# Simulador_Sensor_Hall.net
KiCad netlist of a schematic drawn in EAGLE
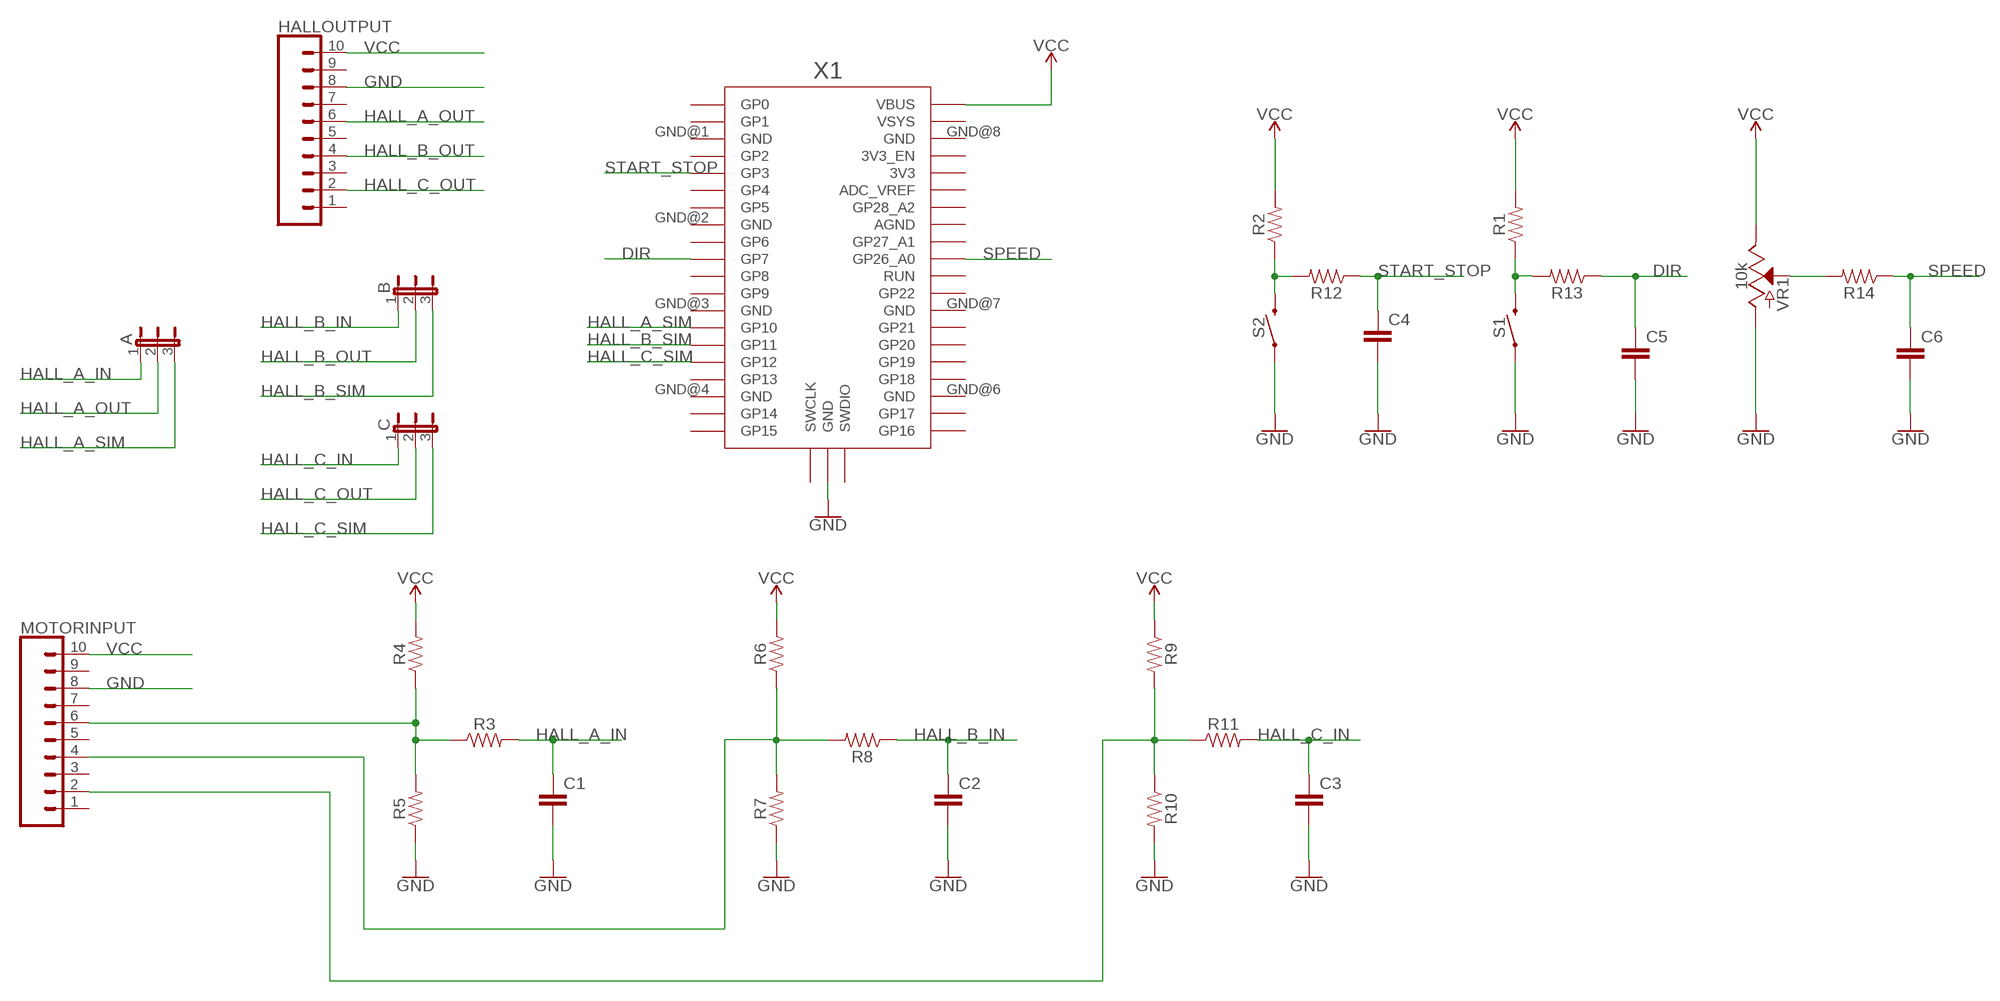
[diagram p0: schematic, sheet 1]

(export (version "E")
  (design (tool "Eeschema 10.0.6"))
  (components
    (comp (ref "A")
      (value "JP2E")
      (footprint "eagle-import:JP2")
      (libsource (lib "eagle-import") (part "JP2E"))
    )
    (comp (ref "B")
      (value "JP2E")
      (footprint "eagle-import:JP2")
      (libsource (lib "eagle-import") (part "JP2E"))
    )
    (comp (ref "C")
      (value "JP2E")
      (footprint "eagle-import:JP2")
      (libsource (lib "eagle-import") (part "JP2E"))
    )
    (comp (ref "C1")
      (value "C-EUC0805K")
      (footprint "eagle-import:C0805K")
      (libsource (lib "eagle-import") (part "C-EUC0805K"))
    )
    (comp (ref "C2")
      (value "C-EUC0805K")
      (footprint "eagle-import:C0805K")
      (libsource (lib "eagle-import") (part "C-EUC0805K"))
    )
    (comp (ref "C3")
      (value "C-EUC0805K")
      (footprint "eagle-import:C0805K")
      (libsource (lib "eagle-import") (part "C-EUC0805K"))
    )
    (comp (ref "C4")
      (value "C-EUC0805K")
      (footprint "eagle-import:C0805K")
      (libsource (lib "eagle-import") (part "C-EUC0805K"))
    )
    (comp (ref "C5")
      (value "C-EUC0805K")
      (footprint "eagle-import:C0805K")
      (libsource (lib "eagle-import") (part "C-EUC0805K"))
    )
    (comp (ref "C6")
      (value "C-EUC0805K")
      (footprint "eagle-import:C0805K")
      (libsource (lib "eagle-import") (part "C-EUC0805K"))
    )
    (comp (ref "HALLOUTPUT")
      (value "CONN_10\"")
      (footprint "eagle-import:1X10")
      (libsource (lib "eagle-import") (part "CONN_10{dblquote}"))
    )
    (comp (ref "MOTORINPUT")
      (value "CONN_10\"")
      (footprint "eagle-import:1X10")
      (libsource (lib "eagle-import") (part "CONN_10{dblquote}"))
    )
    (comp (ref "R1")
      (value "RESISTOR0805")
      (footprint "eagle-import:0805")
      (libsource (lib "eagle-import") (part "RESISTOR0805"))
    )
    (comp (ref "R2")
      (value "RESISTOR0805")
      (footprint "eagle-import:0805")
      (libsource (lib "eagle-import") (part "RESISTOR0805"))
    )
    (comp (ref "R3")
      (value "RESISTOR0805")
      (footprint "eagle-import:0805")
      (libsource (lib "eagle-import") (part "RESISTOR0805"))
    )
    (comp (ref "R4")
      (value "RESISTOR0805")
      (footprint "eagle-import:0805")
      (libsource (lib "eagle-import") (part "RESISTOR0805"))
    )
    (comp (ref "R5")
      (value "RESISTOR0805")
      (footprint "eagle-import:0805")
      (libsource (lib "eagle-import") (part "RESISTOR0805"))
    )
    (comp (ref "R6")
      (value "RESISTOR0805")
      (footprint "eagle-import:0805")
      (libsource (lib "eagle-import") (part "RESISTOR0805"))
    )
    (comp (ref "R7")
      (value "RESISTOR0805")
      (footprint "eagle-import:0805")
      (libsource (lib "eagle-import") (part "RESISTOR0805"))
    )
    (comp (ref "R8")
      (value "RESISTOR0805")
      (footprint "eagle-import:0805")
      (libsource (lib "eagle-import") (part "RESISTOR0805"))
    )
    (comp (ref "R9")
      (value "RESISTOR0805")
      (footprint "eagle-import:0805")
      (libsource (lib "eagle-import") (part "RESISTOR0805"))
    )
    (comp (ref "R10")
      (value "RESISTOR0805")
      (footprint "eagle-import:0805")
      (libsource (lib "eagle-import") (part "RESISTOR0805"))
    )
    (comp (ref "R11")
      (value "RESISTOR0805")
      (footprint "eagle-import:0805")
      (libsource (lib "eagle-import") (part "RESISTOR0805"))
    )
    (comp (ref "R12")
      (value "RESISTOR0805")
      (footprint "eagle-import:0805")
      (libsource (lib "eagle-import") (part "RESISTOR0805"))
    )
    (comp (ref "R13")
      (value "RESISTOR0805")
      (footprint "eagle-import:0805")
      (libsource (lib "eagle-import") (part "RESISTOR0805"))
    )
    (comp (ref "R14")
      (value "RESISTOR0805")
      (footprint "eagle-import:0805")
      (libsource (lib "eagle-import") (part "RESISTOR0805"))
    )
    (comp (ref "S1")
      (value "MOMENTARY-SWITCH-SPST-SMD-6.2MM-TALL")
      (footprint "eagle-import:TACTILE_SWITCH_SMD_6.2MM_TALL")
      (libsource (lib "eagle-import") (part "MOMENTARY-SWITCH-SPST-SMD-6.2MM-TALL"))
    )
    (comp (ref "S2")
      (value "MOMENTARY-SWITCH-SPST-SMD-6.2MM-TALL")
      (footprint "eagle-import:TACTILE_SWITCH_SMD_6.2MM_TALL")
      (libsource (lib "eagle-import") (part "MOMENTARY-SWITCH-SPST-SMD-6.2MM-TALL"))
    )
    (comp (ref "VR1")
      (value "10k")
      (footprint "eagle-import:POT-PTH-ALPS")
      (libsource (lib "eagle-import") (part "POTENTIOMETER-PTH-9MM-1/20W-20%"))
    )
    (comp (ref "X1")
      (value "RPI_PICO_IG-TH")
      (footprint "eagle-import:RPI_PICO_TH")
      (libsource (lib "eagle-import") (part "RPI_PICO_IG-TH"))
    )
  )
  (nets
    (net (code "1") (name "/DIR") (class "Default")
      (node (ref "C5") (pin "1") (pinfunction "1_1") (pintype "passive"))
      (node (ref "R13") (pin "1") (pinfunction "1_1") (pintype "passive"))
      (node (ref "X1") (pin "GP7") (pinfunction "GP7_GP7") (pintype "bidirectional"))
    )
    (net (code "2") (name "/HALL_A_IN") (class "Default")
      (node (ref "A") (pin "1") (pinfunction "1_1") (pintype "passive"))
      (node (ref "C1") (pin "1") (pinfunction "1_1") (pintype "passive"))
      (node (ref "R3") (pin "2") (pinfunction "2_2") (pintype "passive"))
    )
    (net (code "3") (name "/HALL_A_OUT") (class "Default")
      (node (ref "A") (pin "2") (pinfunction "2_2") (pintype "passive"))
      (node (ref "HALLOUTPUT") (pin "6") (pinfunction "6_6") (pintype "passive"))
    )
    (net (code "4") (name "/HALL_A_SIM") (class "Default")
      (node (ref "A") (pin "3") (pinfunction "3_3") (pintype "passive"))
      (node (ref "X1") (pin "GP10") (pinfunction "GP10_GP10") (pintype "bidirectional"))
    )
    (net (code "5") (name "/HALL_B_IN") (class "Default")
      (node (ref "B") (pin "1") (pinfunction "1_1") (pintype "passive"))
      (node (ref "C2") (pin "1") (pinfunction "1_1") (pintype "passive"))
      (node (ref "R8") (pin "1") (pinfunction "1_1") (pintype "passive"))
    )
    (net (code "6") (name "/HALL_B_OUT") (class "Default")
      (node (ref "B") (pin "2") (pinfunction "2_2") (pintype "passive"))
      (node (ref "HALLOUTPUT") (pin "4") (pinfunction "4_4") (pintype "passive"))
    )
    (net (code "7") (name "/HALL_B_SIM") (class "Default")
      (node (ref "B") (pin "3") (pinfunction "3_3") (pintype "passive"))
      (node (ref "X1") (pin "GP11") (pinfunction "GP11_GP11") (pintype "bidirectional"))
    )
    (net (code "8") (name "/HALL_C_IN") (class "Default")
      (node (ref "C") (pin "1") (pinfunction "1_1") (pintype "passive"))
      (node (ref "C3") (pin "1") (pinfunction "1_1") (pintype "passive"))
      (node (ref "R11") (pin "2") (pinfunction "2_2") (pintype "passive"))
    )
    (net (code "9") (name "/HALL_C_OUT") (class "Default")
      (node (ref "C") (pin "2") (pinfunction "2_2") (pintype "passive"))
      (node (ref "HALLOUTPUT") (pin "2") (pinfunction "2_2") (pintype "passive"))
    )
    (net (code "10") (name "/HALL_C_SIM") (class "Default")
      (node (ref "C") (pin "3") (pinfunction "3_3") (pintype "passive"))
      (node (ref "X1") (pin "GP12") (pinfunction "GP12_GP12") (pintype "bidirectional"))
    )
    (net (code "11") (name "/SPEED") (class "Default")
      (node (ref "C6") (pin "1") (pinfunction "1_1") (pintype "passive"))
      (node (ref "R14") (pin "1") (pinfunction "1_1") (pintype "passive"))
      (node (ref "X1") (pin "GP26_A0") (pinfunction "GP26_A0_GP26_A0") (pintype "bidirectional"))
    )
    (net (code "12") (name "/START_STOP") (class "Default")
      (node (ref "C4") (pin "1") (pinfunction "1_1") (pintype "passive"))
      (node (ref "R12") (pin "1") (pinfunction "1_1") (pintype "passive"))
      (node (ref "X1") (pin "GP3") (pinfunction "GP3_GP3") (pintype "bidirectional"))
    )
    (net (code "13") (name "GND") (class "Default")
      (node (ref "C1") (pin "2") (pinfunction "2_2") (pintype "passive"))
      (node (ref "C2") (pin "2") (pinfunction "2_2") (pintype "passive"))
      (node (ref "C3") (pin "2") (pinfunction "2_2") (pintype "passive"))
      (node (ref "C4") (pin "2") (pinfunction "2_2") (pintype "passive"))
      (node (ref "C5") (pin "2") (pinfunction "2_2") (pintype "passive"))
      (node (ref "C6") (pin "2") (pinfunction "2_2") (pintype "passive"))
      (node (ref "HALLOUTPUT") (pin "8") (pinfunction "8_8") (pintype "passive"))
      (node (ref "MOTORINPUT") (pin "8") (pinfunction "8_8") (pintype "passive"))
      (node (ref "R10") (pin "2") (pinfunction "2_2") (pintype "passive"))
      (node (ref "R5") (pin "1") (pinfunction "1_1") (pintype "passive"))
      (node (ref "R7") (pin "1") (pinfunction "1_1") (pintype "passive"))
      (node (ref "S1") (pin "A2") (pinfunction "1_A2") (pintype "passive"))
      (node (ref "S2") (pin "A2") (pinfunction "1_A2") (pintype "passive"))
      (node (ref "VR1") (pin "P$3") (pinfunction "A_P$3") (pintype "passive"))
      (node (ref "X1") (pin "GND@5") (pinfunction "GND_GND@5") (pintype "bidirectional"))
    )
    (net (code "14") (name "Net-(MOTORINPUT-Pad2)") (class "Default")
      (node (ref "MOTORINPUT") (pin "2") (pinfunction "2_2") (pintype "passive"))
      (node (ref "R10") (pin "1") (pinfunction "1_1") (pintype "passive"))
      (node (ref "R11") (pin "1") (pinfunction "1_1") (pintype "passive"))
      (node (ref "R9") (pin "2") (pinfunction "2_2") (pintype "passive"))
    )
    (net (code "15") (name "Net-(MOTORINPUT-Pad4)") (class "Default")
      (node (ref "MOTORINPUT") (pin "4") (pinfunction "4_4") (pintype "passive"))
      (node (ref "R6") (pin "1") (pinfunction "1_1") (pintype "passive"))
      (node (ref "R7") (pin "2") (pinfunction "2_2") (pintype "passive"))
      (node (ref "R8") (pin "2") (pinfunction "2_2") (pintype "passive"))
    )
    (net (code "16") (name "Net-(MOTORINPUT-Pad6)") (class "Default")
      (node (ref "MOTORINPUT") (pin "6") (pinfunction "6_6") (pintype "passive"))
      (node (ref "R3") (pin "1") (pinfunction "1_1") (pintype "passive"))
      (node (ref "R4") (pin "1") (pinfunction "1_1") (pintype "passive"))
      (node (ref "R5") (pin "2") (pinfunction "2_2") (pintype "passive"))
    )
    (net (code "17") (name "Net-(S1-2)") (class "Default")
      (node (ref "R1") (pin "1") (pinfunction "1_1") (pintype "passive"))
      (node (ref "R13") (pin "2") (pinfunction "2_2") (pintype "passive"))
      (node (ref "S1") (pin "B2") (pinfunction "2_B2") (pintype "passive"))
    )
    (net (code "18") (name "Net-(S2-2)") (class "Default")
      (node (ref "R12") (pin "2") (pinfunction "2_2") (pintype "passive"))
      (node (ref "R2") (pin "1") (pinfunction "1_1") (pintype "passive"))
      (node (ref "S2") (pin "B2") (pinfunction "2_B2") (pintype "passive"))
    )
    (net (code "19") (name "Net-(VR1-S)") (class "Default")
      (node (ref "R14") (pin "2") (pinfunction "2_2") (pintype "passive"))
      (node (ref "VR1") (pin "P$2") (pinfunction "S_P$2") (pintype "passive"))
    )
    (net (code "20") (name "VCC") (class "Default")
      (node (ref "HALLOUTPUT") (pin "10") (pinfunction "10_10") (pintype "passive"))
      (node (ref "MOTORINPUT") (pin "10") (pinfunction "10_10") (pintype "passive"))
      (node (ref "R1") (pin "2") (pinfunction "2_2") (pintype "passive"))
      (node (ref "R2") (pin "2") (pinfunction "2_2") (pintype "passive"))
      (node (ref "R4") (pin "2") (pinfunction "2_2") (pintype "passive"))
      (node (ref "R6") (pin "2") (pinfunction "2_2") (pintype "passive"))
      (node (ref "R9") (pin "1") (pinfunction "1_1") (pintype "passive"))
      (node (ref "VR1") (pin "P$1") (pinfunction "E_P$1") (pintype "passive"))
      (node (ref "X1") (pin "VBUS") (pinfunction "VBUS_VBUS") (pintype "bidirectional"))
    )
    (net (code "21") (name "unconnected-(HALLOUTPUT-Pad1)") (class "Default")
      (node (ref "HALLOUTPUT") (pin "1") (pinfunction "1_1") (pintype "passive"))
    )
    (net (code "22") (name "unconnected-(HALLOUTPUT-Pad3)") (class "Default")
      (node (ref "HALLOUTPUT") (pin "3") (pinfunction "3_3") (pintype "passive"))
    )
    (net (code "23") (name "unconnected-(HALLOUTPUT-Pad5)") (class "Default")
      (node (ref "HALLOUTPUT") (pin "5") (pinfunction "5_5") (pintype "passive"))
    )
    (net (code "24") (name "unconnected-(HALLOUTPUT-Pad7)") (class "Default")
      (node (ref "HALLOUTPUT") (pin "7") (pinfunction "7_7") (pintype "passive"))
    )
    (net (code "25") (name "unconnected-(HALLOUTPUT-Pad9)") (class "Default")
      (node (ref "HALLOUTPUT") (pin "9") (pinfunction "9_9") (pintype "passive"))
    )
    (net (code "26") (name "unconnected-(MOTORINPUT-Pad1)") (class "Default")
      (node (ref "MOTORINPUT") (pin "1") (pinfunction "1_1") (pintype "passive"))
    )
    (net (code "27") (name "unconnected-(MOTORINPUT-Pad3)") (class "Default")
      (node (ref "MOTORINPUT") (pin "3") (pinfunction "3_3") (pintype "passive"))
    )
    (net (code "28") (name "unconnected-(MOTORINPUT-Pad5)") (class "Default")
      (node (ref "MOTORINPUT") (pin "5") (pinfunction "5_5") (pintype "passive"))
    )
    (net (code "29") (name "unconnected-(MOTORINPUT-Pad7)") (class "Default")
      (node (ref "MOTORINPUT") (pin "7") (pinfunction "7_7") (pintype "passive"))
    )
    (net (code "30") (name "unconnected-(MOTORINPUT-Pad9)") (class "Default")
      (node (ref "MOTORINPUT") (pin "9") (pinfunction "9_9") (pintype "passive"))
    )
    (net (code "31") (name "unconnected-(X1-GND-PadGND@1)") (class "Default")
      (node (ref "X1") (pin "GND@1") (pinfunction "GND_GND@1") (pintype "bidirectional"))
    )
    (net (code "32") (name "unconnected-(X1-GND-PadGND@2)") (class "Default")
      (node (ref "X1") (pin "GND@2") (pinfunction "GND_GND@2") (pintype "bidirectional"))
    )
    (net (code "33") (name "unconnected-(X1-GND-PadGND@3)") (class "Default")
      (node (ref "X1") (pin "GND@3") (pinfunction "GND_GND@3") (pintype "bidirectional"))
    )
    (net (code "34") (name "unconnected-(X1-GND-PadGND@4)") (class "Default")
      (node (ref "X1") (pin "GND@4") (pinfunction "GND_GND@4") (pintype "bidirectional"))
    )
    (net (code "35") (name "unconnected-(X1-GND-PadGND@6)") (class "Default")
      (node (ref "X1") (pin "GND@6") (pinfunction "GND_GND@6") (pintype "bidirectional"))
    )
    (net (code "36") (name "unconnected-(X1-GND-PadGND@7)") (class "Default")
      (node (ref "X1") (pin "GND@7") (pinfunction "GND_GND@7") (pintype "bidirectional"))
    )
    (net (code "37") (name "unconnected-(X1-GND-PadGND@8)") (class "Default")
      (node (ref "X1") (pin "GND@8") (pinfunction "GND_GND@8") (pintype "bidirectional"))
    )
    (net (code "38") (name "unconnected-(X1-Pad3V3)") (class "Default")
      (node (ref "X1") (pin "3V3") (pinfunction "3V3_3V3") (pintype "bidirectional"))
    )
    (net (code "39") (name "unconnected-(X1-Pad3V3_EN)") (class "Default")
      (node (ref "X1") (pin "3V3_EN") (pinfunction "3V3_EN_3V3_EN") (pintype "bidirectional"))
    )
    (net (code "40") (name "unconnected-(X1-PadADC_VREF)") (class "Default")
      (node (ref "X1") (pin "ADC_VREF") (pinfunction "ADC_VREF_ADC_VREF") (pintype "bidirectional"))
    )
    (net (code "41") (name "unconnected-(X1-PadAGND)") (class "Default")
      (node (ref "X1") (pin "AGND") (pinfunction "AGND_AGND") (pintype "bidirectional"))
    )
    (net (code "42") (name "unconnected-(X1-PadGP0)") (class "Default")
      (node (ref "X1") (pin "GP0") (pinfunction "GP0_GP0") (pintype "bidirectional"))
    )
    (net (code "43") (name "unconnected-(X1-PadGP1)") (class "Default")
      (node (ref "X1") (pin "GP1") (pinfunction "GP1_GP1") (pintype "bidirectional"))
    )
    (net (code "44") (name "unconnected-(X1-PadGP2)") (class "Default")
      (node (ref "X1") (pin "GP2") (pinfunction "GP2_GP2") (pintype "bidirectional"))
    )
    (net (code "45") (name "unconnected-(X1-PadGP4)") (class "Default")
      (node (ref "X1") (pin "GP4") (pinfunction "GP4_GP4") (pintype "bidirectional"))
    )
    (net (code "46") (name "unconnected-(X1-PadGP5)") (class "Default")
      (node (ref "X1") (pin "GP5") (pinfunction "GP5_GP5") (pintype "bidirectional"))
    )
    (net (code "47") (name "unconnected-(X1-PadGP6)") (class "Default")
      (node (ref "X1") (pin "GP6") (pinfunction "GP6_GP6") (pintype "bidirectional"))
    )
    (net (code "48") (name "unconnected-(X1-PadGP8)") (class "Default")
      (node (ref "X1") (pin "GP8") (pinfunction "GP8_GP8") (pintype "bidirectional"))
    )
    (net (code "49") (name "unconnected-(X1-PadGP9)") (class "Default")
      (node (ref "X1") (pin "GP9") (pinfunction "GP9_GP9") (pintype "bidirectional"))
    )
    (net (code "50") (name "unconnected-(X1-PadGP13)") (class "Default")
      (node (ref "X1") (pin "GP13") (pinfunction "GP13_GP13") (pintype "bidirectional"))
    )
    (net (code "51") (name "unconnected-(X1-PadGP14)") (class "Default")
      (node (ref "X1") (pin "GP14") (pinfunction "GP14_GP14") (pintype "bidirectional"))
    )
    (net (code "52") (name "unconnected-(X1-PadGP15)") (class "Default")
      (node (ref "X1") (pin "GP15") (pinfunction "GP15_GP15") (pintype "bidirectional"))
    )
    (net (code "53") (name "unconnected-(X1-PadGP16)") (class "Default")
      (node (ref "X1") (pin "GP16") (pinfunction "GP16_GP16") (pintype "bidirectional"))
    )
    (net (code "54") (name "unconnected-(X1-PadGP17)") (class "Default")
      (node (ref "X1") (pin "GP17") (pinfunction "GP17_GP17") (pintype "bidirectional"))
    )
    (net (code "55") (name "unconnected-(X1-PadGP18)") (class "Default")
      (node (ref "X1") (pin "GP18") (pinfunction "GP18_GP18") (pintype "bidirectional"))
    )
    (net (code "56") (name "unconnected-(X1-PadGP19)") (class "Default")
      (node (ref "X1") (pin "GP19") (pinfunction "GP19_GP19") (pintype "bidirectional"))
    )
    (net (code "57") (name "unconnected-(X1-PadGP20)") (class "Default")
      (node (ref "X1") (pin "GP20") (pinfunction "GP20_GP20") (pintype "bidirectional"))
    )
    (net (code "58") (name "unconnected-(X1-PadGP21)") (class "Default")
      (node (ref "X1") (pin "GP21") (pinfunction "GP21_GP21") (pintype "bidirectional"))
    )
    (net (code "59") (name "unconnected-(X1-PadGP22)") (class "Default")
      (node (ref "X1") (pin "GP22") (pinfunction "GP22_GP22") (pintype "bidirectional"))
    )
    (net (code "60") (name "unconnected-(X1-PadGP27_A1)") (class "Default")
      (node (ref "X1") (pin "GP27_A1") (pinfunction "GP27_A1_GP27_A1") (pintype "bidirectional"))
    )
    (net (code "61") (name "unconnected-(X1-PadGP28_A2)") (class "Default")
      (node (ref "X1") (pin "GP28_A2") (pinfunction "GP28_A2_GP28_A2") (pintype "bidirectional"))
    )
    (net (code "62") (name "unconnected-(X1-PadRUN)") (class "Default")
      (node (ref "X1") (pin "RUN") (pinfunction "RUN_RUN") (pintype "bidirectional"))
    )
    (net (code "63") (name "unconnected-(X1-PadSWCLK)") (class "Default")
      (node (ref "X1") (pin "SWCLK") (pinfunction "SWCLK_SWCLK") (pintype "bidirectional"))
    )
    (net (code "64") (name "unconnected-(X1-PadSWDIO)") (class "Default")
      (node (ref "X1") (pin "SWDIO") (pinfunction "SWDIO_SWDIO") (pintype "bidirectional"))
    )
    (net (code "65") (name "unconnected-(X1-PadVSYS)") (class "Default")
      (node (ref "X1") (pin "VSYS") (pinfunction "VSYS_VSYS") (pintype "bidirectional"))
    )
  )
)
